# LED_TRIANGEL.net
KiCad netlist of a schematic drawn in Altium Designer
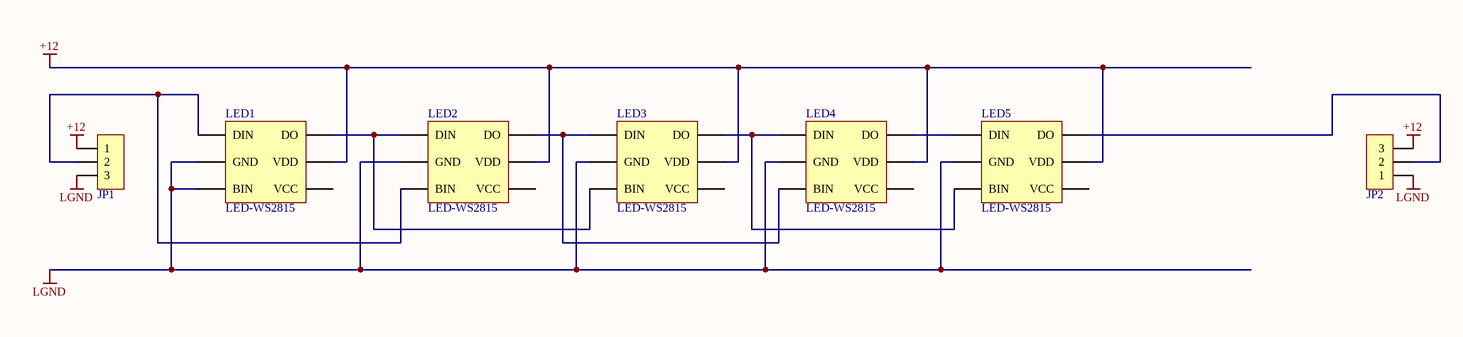
[diagram p0: LED_TRIANGEL.SchDoc]

(export (version "E")
  (design (tool "Eeschema 10.0.6"))
  (components
    (comp (ref "JP1")
      (value "HDR-1X3")
      (footprint "ZH1.5-WS-3P")
      (description "3P接插件")
      (fields (field (name "版权归属") "源创客"))
      (libsource (lib "") (part "Header 3_1"))
    )
    (comp (ref "JP2")
      (value "HDR-1X3")
      (footprint "ZH1.5-WS-3P")
      (description "3P接插件")
      (fields (field (name "版权归属") "源创客"))
      (libsource (lib "4.4   - 接插件-脚距1.5") (part "Header 3"))
    )
    (comp (ref "LED1")
      (value "LED-WS2815")
      (footprint "LED 5050")
      (description "三基色LED")
      (fields (field (name "版权归属") "源创客"))
      (libsource (lib "9.1   - LED") (part "LED-WS2815"))
    )
    (comp (ref "LED2")
      (value "LED-WS2815")
      (footprint "LED 5050")
      (description "三基色LED")
      (fields (field (name "版权归属") "源创客"))
      (libsource (lib "9.1   - LED") (part "LED-WS2815"))
    )
    (comp (ref "LED3")
      (value "LED-WS2815")
      (footprint "LED 5050")
      (description "三基色LED")
      (fields (field (name "版权归属") "源创客"))
      (libsource (lib "9.1   - LED") (part "LED-WS2815"))
    )
    (comp (ref "LED4")
      (value "LED-WS2815")
      (footprint "LED 5050")
      (description "三基色LED")
      (fields (field (name "版权归属") "源创客"))
      (libsource (lib "9.1   - LED") (part "LED-WS2815"))
    )
    (comp (ref "LED5")
      (value "LED-WS2815")
      (footprint "LED 5050")
      (description "三基色LED")
      (fields (field (name "版权归属") "源创客"))
      (libsource (lib "9.1   - LED") (part "LED-WS2815"))
    )
  )
  (nets
    (net (code "1") (name "+12") (class "Default")
      (node (ref "JP1") (pin "1") (pinfunction "1_1") (pintype "passive"))
      (node (ref "JP2") (pin "3") (pinfunction "3_3") (pintype "passive"))
      (node (ref "LED1") (pin "4") (pinfunction "VDD_4") (pintype "passive"))
      (node (ref "LED2") (pin "4") (pinfunction "VDD_4") (pintype "passive"))
      (node (ref "LED3") (pin "4") (pinfunction "VDD_4") (pintype "passive"))
      (node (ref "LED4") (pin "4") (pinfunction "VDD_4") (pintype "passive"))
      (node (ref "LED5") (pin "4") (pinfunction "VDD_4") (pintype "passive"))
    )
    (net (code "2") (name "LGND") (class "Default")
      (node (ref "JP1") (pin "3") (pinfunction "3_3") (pintype "passive"))
      (node (ref "JP2") (pin "1") (pinfunction "1_1") (pintype "passive"))
      (node (ref "LED1") (pin "3") (pinfunction "GND_3") (pintype "passive"))
      (node (ref "LED1") (pin "5") (pinfunction "BIN_5") (pintype "passive"))
      (node (ref "LED2") (pin "3") (pinfunction "GND_3") (pintype "passive"))
      (node (ref "LED3") (pin "3") (pinfunction "GND_3") (pintype "passive"))
      (node (ref "LED4") (pin "3") (pinfunction "GND_3") (pintype "passive"))
      (node (ref "LED5") (pin "3") (pinfunction "GND_3") (pintype "passive"))
    )
    (net (code "3") (name "Net-(LED1-DIN)") (class "Default")
      (node (ref "JP1") (pin "2") (pinfunction "2_2") (pintype "passive"))
      (node (ref "LED1") (pin "1") (pinfunction "DIN_1") (pintype "passive"))
      (node (ref "LED2") (pin "5") (pinfunction "BIN_5") (pintype "passive"))
    )
    (net (code "4") (name "Net-(LED1-DO)") (class "Default")
      (node (ref "LED1") (pin "2") (pinfunction "DO_2") (pintype "passive"))
      (node (ref "LED2") (pin "1") (pinfunction "DIN_1") (pintype "passive"))
      (node (ref "LED3") (pin "5") (pinfunction "BIN_5") (pintype "passive"))
    )
    (net (code "5") (name "Net-(LED2-DO)") (class "Default")
      (node (ref "LED2") (pin "2") (pinfunction "DO_2") (pintype "passive"))
      (node (ref "LED3") (pin "1") (pinfunction "DIN_1") (pintype "passive"))
      (node (ref "LED4") (pin "5") (pinfunction "BIN_5") (pintype "passive"))
    )
    (net (code "6") (name "Net-(LED3-DO)") (class "Default")
      (node (ref "LED3") (pin "2") (pinfunction "DO_2") (pintype "passive"))
      (node (ref "LED4") (pin "1") (pinfunction "DIN_1") (pintype "passive"))
      (node (ref "LED5") (pin "5") (pinfunction "BIN_5") (pintype "passive"))
    )
    (net (code "7") (name "Net-(LED4-DO)") (class "Default")
      (node (ref "LED4") (pin "2") (pinfunction "DO_2") (pintype "passive"))
      (node (ref "LED5") (pin "1") (pinfunction "DIN_1") (pintype "passive"))
    )
    (net (code "8") (name "Net-(LED5-DO)") (class "Default")
      (node (ref "JP2") (pin "2") (pinfunction "2_2") (pintype "passive"))
      (node (ref "LED5") (pin "2") (pinfunction "DO_2") (pintype "passive"))
    )
    (net (code "9") (name "unconnected-(LED1-VCC-Pad6)") (class "Default")
      (node (ref "LED1") (pin "6") (pinfunction "VCC_6") (pintype "passive"))
    )
    (net (code "10") (name "unconnected-(LED2-VCC-Pad6)") (class "Default")
      (node (ref "LED2") (pin "6") (pinfunction "VCC_6") (pintype "passive"))
    )
    (net (code "11") (name "unconnected-(LED3-VCC-Pad6)") (class "Default")
      (node (ref "LED3") (pin "6") (pinfunction "VCC_6") (pintype "passive"))
    )
    (net (code "12") (name "unconnected-(LED4-VCC-Pad6)") (class "Default")
      (node (ref "LED4") (pin "6") (pinfunction "VCC_6") (pintype "passive"))
    )
    (net (code "13") (name "unconnected-(LED5-VCC-Pad6)") (class "Default")
      (node (ref "LED5") (pin "6") (pinfunction "VCC_6") (pintype "passive"))
    )
  )
)
